# SCH.net
KiCad netlist of a schematic drawn in Altium Designer
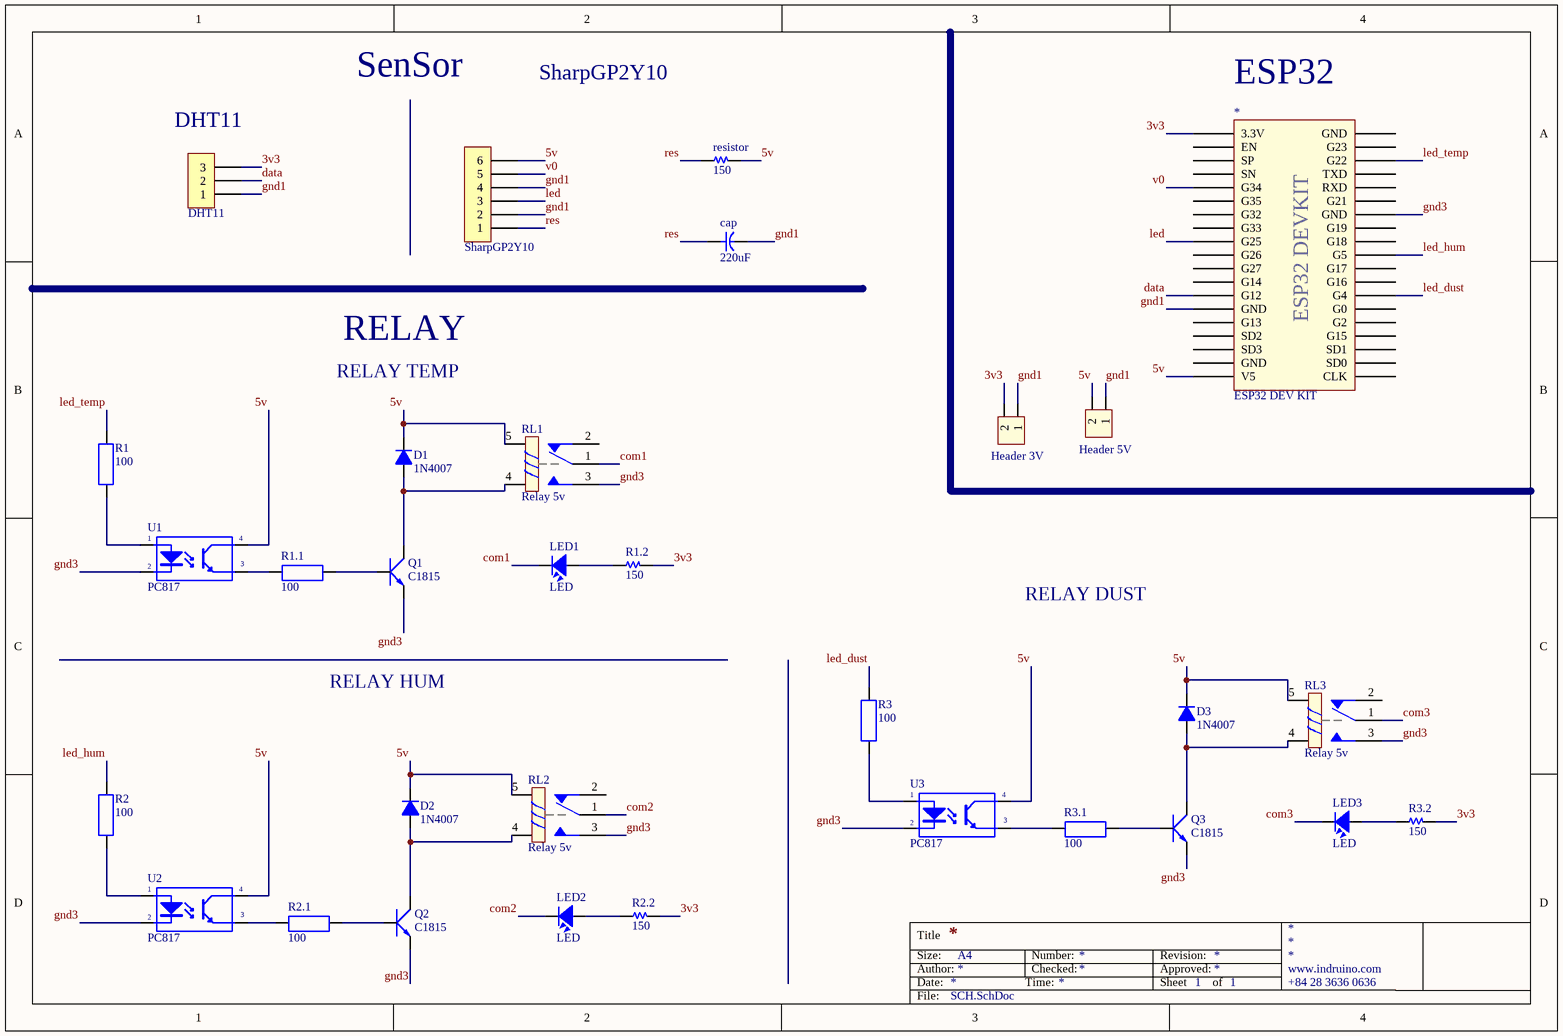
[diagram p0: SCH.SchDoc]

(export (version "E")
  (design (tool "Eeschema 10.0.6"))
  (components
    (comp (ref "*")
      (value "ESP32 DEV KIT")
      (footprint "ESP32 DEVKIT")
      (libsource (lib "Module") (part "ESP32 DEV KIT"))
    )
    (comp (ref "cap")
      (value "220uF")
      (footprint "CYL/D.250/LS.100")
      (description "Capacitor pol")
      (libsource (lib "chipfc_libs") (part "Capacitor"))
    )
    (comp (ref "D1")
      (value "1N4007")
      (footprint "D0.5A")
      (description "Diode 1A")
      (libsource (lib "SCH_Lib_Devzone") (part "D1A"))
    )
    (comp (ref "D2")
      (value "1N4007")
      (footprint "D0.5A")
      (description "Diode 1A")
      (libsource (lib "SCH_Lib_Devzone") (part "D1A"))
    )
    (comp (ref "D3")
      (value "1N4007")
      (footprint "D0.5A")
      (description "Diode 1A")
      (libsource (lib "SCH_Lib_Devzone") (part "D1A"))
    )
    (comp (ref "DHT11")
      (value "DHT11")
      (footprint "XH2.54M-3")
      (description "Cắm")
      (libsource (lib "Header") (part "Header 3P 2.54 Duc Thang"))
    )
    (comp (ref "Header 3V")
      (value "Header 3V")
      (footprint "XH2.54M-2")
      (description "Cắm")
      (libsource (lib "Header") (part "Header 2P 2.54 Duc Thang"))
    )
    (comp (ref "Header 5V")
      (value "Header 5V")
      (footprint "XH2.54M-2")
      (description "Cắm")
      (libsource (lib "Header") (part "Header 2P 2.54 Duc Thang"))
    )
    (comp (ref "LED1")
      (value "LED")
      (footprint "led5mm_yellow")
      (description "LED Single colour Green and Red")
      (libsource (lib "Compiled_Devzone") (part "LED"))
    )
    (comp (ref "LED2")
      (value "LED")
      (footprint "led5mm_yellow")
      (description "LED Single colour Green and Red")
      (libsource (lib "Compiled_Devzone") (part "LED"))
    )
    (comp (ref "LED3")
      (value "LED")
      (footprint "led5mm_yellow")
      (description "LED Single colour Green and Red")
      (libsource (lib "Compiled_Devzone") (part "LED"))
    )
    (comp (ref "Q1")
      (value "C1815")
      (footprint "QTO-92")
      (description "NPN 600mW, ECB")
      (libsource (lib "SCH_Lib_Devzone") (part "C1815"))
    )
    (comp (ref "Q2")
      (value "C1815")
      (footprint "QTO-92")
      (description "NPN 600mW, ECB")
      (libsource (lib "SCH_Lib_Devzone") (part "C1815"))
    )
    (comp (ref "Q3")
      (value "C1815")
      (footprint "QTO-92")
      (description "NPN 600mW, ECB")
      (libsource (lib "SCH_Lib_Devzone") (part "C1815"))
    )
    (comp (ref "R1")
      (value "100")
      (footprint "Res_15mm")
      (description "Resistor 1W")
      (libsource (lib "SCH_Lib_Devzone") (part "R1W"))
    )
    (comp (ref "R1.1")
      (value "100")
      (footprint "Res_15mm")
      (description "Resistor 1W")
      (libsource (lib "SCH_Lib_Devzone") (part "R1W"))
    )
    (comp (ref "R1.2")
      (value "150")
      (footprint "R 1/4W/300")
      (description "Resistor")
      (libsource (lib "chipfc_libs") (part "Resistor"))
    )
    (comp (ref "R2")
      (value "100")
      (footprint "Res_15mm")
      (description "Resistor 1W")
      (libsource (lib "SCH_Lib_Devzone") (part "R1W"))
    )
    (comp (ref "R2.1")
      (value "100")
      (footprint "Res_15mm")
      (description "Resistor 1W")
      (libsource (lib "SCH_Lib_Devzone") (part "R1W"))
    )
    (comp (ref "R2.2")
      (value "150")
      (footprint "R 1/4W/300")
      (description "Resistor")
      (libsource (lib "chipfc_libs") (part "Resistor"))
    )
    (comp (ref "R3")
      (value "100")
      (footprint "Res_15mm")
      (description "Resistor 1W")
      (libsource (lib "SCH_Lib_Devzone") (part "R1W"))
    )
    (comp (ref "R3.1")
      (value "100")
      (footprint "Res_15mm")
      (description "Resistor 1W")
      (libsource (lib "SCH_Lib_Devzone") (part "R1W"))
    )
    (comp (ref "R3.2")
      (value "150")
      (footprint "R 1/4W/300")
      (description "Resistor")
      (libsource (lib "chipfc_libs") (part "Resistor"))
    )
    (comp (ref "resistor")
      (value "150")
      (footprint "R 1/4W/300")
      (description "Resistor")
      (libsource (lib "chipfc_libs") (part "Resistor"))
    )
    (comp (ref "RL1")
      (value "Relay 5v")
      (footprint "RL_SPDT_10A")
      (description "Relay SPDT,10A - 12VDC 5 Pin")
      (libsource (lib "Compiled_Devzone") (part "Relay 1"))
    )
    (comp (ref "RL2")
      (value "Relay 5v")
      (footprint "RL_SPDT_10A")
      (description "Relay SPDT,10A - 12VDC 5 Pin")
      (libsource (lib "Compiled_Devzone") (part "Relay 1"))
    )
    (comp (ref "RL3")
      (value "Relay 5v")
      (footprint "RL_SPDT_10A")
      (description "Relay SPDT,10A - 12VDC 5 Pin")
      (libsource (lib "Compiled_Devzone") (part "Relay 1"))
    )
    (comp (ref "SharpGP2Y10")
      (value "SharpGP2Y10")
      (footprint "XH2.54M-6")
      (description "Cắm")
      (libsource (lib "Header") (part "Header 6P 2.54 Duc Thang"))
    )
    (comp (ref "U1")
      (value "PC817")
      (footprint "DIP4/W0.3")
      (description "Single Opto")
      (libsource (lib "SCH_Lib_Devzone") (part "PC817"))
    )
    (comp (ref "U2")
      (value "PC817")
      (footprint "DIP4/W0.3")
      (description "Single Opto")
      (libsource (lib "SCH_Lib_Devzone") (part "PC817"))
    )
    (comp (ref "U3")
      (value "PC817")
      (footprint "DIP4/W0.3")
      (description "Single Opto")
      (libsource (lib "SCH_Lib_Devzone") (part "PC817"))
    )
  )
  (nets
    (net (code "1") (name "/3v3") (class "Default")
      (node (ref "*") (pin "1") (pinfunction "3.3V_1") (pintype "passive"))
      (node (ref "DHT11") (pin "3") (pinfunction "3_3") (pintype "passive"))
      (node (ref "Header 3V") (pin "2") (pinfunction "2_2") (pintype "passive"))
      (node (ref "R1.2") (pin "2") (pinfunction "2_2") (pintype "passive"))
      (node (ref "R2.2") (pin "2") (pinfunction "2_2") (pintype "passive"))
      (node (ref "R3.2") (pin "2") (pinfunction "2_2") (pintype "passive"))
    )
    (net (code "2") (name "/5v") (class "Default")
      (node (ref "*") (pin "19") (pinfunction "V5_19") (pintype "passive"))
      (node (ref "D1") (pin "2") (pinfunction "K_2") (pintype "passive"))
      (node (ref "D2") (pin "2") (pinfunction "K_2") (pintype "passive"))
      (node (ref "D3") (pin "2") (pinfunction "K_2") (pintype "passive"))
      (node (ref "Header 5V") (pin "2") (pinfunction "2_2") (pintype "passive"))
      (node (ref "RL1") (pin "5") (pinfunction "5_5") (pintype "passive"))
      (node (ref "RL2") (pin "5") (pinfunction "5_5") (pintype "passive"))
      (node (ref "RL3") (pin "5") (pinfunction "5_5") (pintype "passive"))
      (node (ref "SharpGP2Y10") (pin "6") (pinfunction "6_6") (pintype "passive"))
      (node (ref "U1") (pin "4") (pinfunction "C_4") (pintype "passive"))
      (node (ref "U2") (pin "4") (pinfunction "C_4") (pintype "passive"))
      (node (ref "U3") (pin "4") (pinfunction "C_4") (pintype "passive"))
      (node (ref "resistor") (pin "2") (pinfunction "2_2") (pintype "passive"))
    )
    (net (code "4") (name "/com1") (class "Default")
      (node (ref "LED1") (pin "2") (pinfunction "2_2") (pintype "passive"))
      (node (ref "RL1") (pin "1") (pinfunction "1_1") (pintype "passive"))
    )
    (net (code "5") (name "/com2") (class "Default")
      (node (ref "LED2") (pin "2") (pinfunction "2_2") (pintype "passive"))
      (node (ref "RL2") (pin "1") (pinfunction "1_1") (pintype "passive"))
    )
    (net (code "6") (name "/com3") (class "Default")
      (node (ref "LED3") (pin "2") (pinfunction "2_2") (pintype "passive"))
      (node (ref "RL3") (pin "1") (pinfunction "1_1") (pintype "passive"))
    )
    (net (code "7") (name "/data") (class "Default")
      (node (ref "*") (pin "13") (pinfunction "G12_13") (pintype "passive"))
      (node (ref "DHT11") (pin "2") (pinfunction "2_2") (pintype "passive"))
    )
    (net (code "8") (name "/gnd1") (class "Default")
      (node (ref "*") (pin "14") (pinfunction "GND_14") (pintype "passive"))
      (node (ref "DHT11") (pin "1") (pinfunction "1_1") (pintype "passive"))
      (node (ref "Header 3V") (pin "1") (pinfunction "1_1") (pintype "passive"))
      (node (ref "Header 5V") (pin "1") (pinfunction "1_1") (pintype "passive"))
      (node (ref "SharpGP2Y10") (pin "2") (pinfunction "2_2") (pintype "passive"))
      (node (ref "SharpGP2Y10") (pin "4") (pinfunction "4_4") (pintype "passive"))
      (node (ref "cap") (pin "2") (pinfunction "2_2") (pintype "passive"))
    )
    (net (code "9") (name "/gnd3") (class "Default")
      (node (ref "*") (pin "32") (pinfunction "GND_32") (pintype "passive"))
      (node (ref "Q1") (pin "1") (pinfunction "E_1") (pintype "passive"))
      (node (ref "Q2") (pin "1") (pinfunction "E_1") (pintype "passive"))
      (node (ref "Q3") (pin "1") (pinfunction "E_1") (pintype "passive"))
      (node (ref "RL1") (pin "3") (pinfunction "3_3") (pintype "passive"))
      (node (ref "RL2") (pin "3") (pinfunction "3_3") (pintype "passive"))
      (node (ref "RL3") (pin "3") (pinfunction "3_3") (pintype "passive"))
      (node (ref "U1") (pin "2") (pinfunction "K_2") (pintype "passive"))
      (node (ref "U2") (pin "2") (pinfunction "K_2") (pintype "passive"))
      (node (ref "U3") (pin "2") (pinfunction "K_2") (pintype "passive"))
    )
    (net (code "10") (name "/led") (class "Default")
      (node (ref "*") (pin "9") (pinfunction "G25_9") (pintype "passive"))
      (node (ref "SharpGP2Y10") (pin "3") (pinfunction "3_3") (pintype "passive"))
    )
    (net (code "11") (name "/led_dust") (class "Default")
      (node (ref "*") (pin "26") (pinfunction "G4_26") (pintype "passive"))
      (node (ref "R3") (pin "2") (pinfunction "2_2") (pintype "passive"))
    )
    (net (code "12") (name "/led_hum") (class "Default")
      (node (ref "*") (pin "29") (pinfunction "G5_29") (pintype "passive"))
      (node (ref "R2") (pin "2") (pinfunction "2_2") (pintype "passive"))
    )
    (net (code "13") (name "/led_temp") (class "Default")
      (node (ref "*") (pin "36") (pinfunction "G22_36") (pintype "passive"))
      (node (ref "R1") (pin "2") (pinfunction "2_2") (pintype "passive"))
    )
    (net (code "14") (name "/res") (class "Default")
      (node (ref "SharpGP2Y10") (pin "1") (pinfunction "1_1") (pintype "passive"))
      (node (ref "cap") (pin "1") (pinfunction "1_1") (pintype "passive"))
      (node (ref "resistor") (pin "1") (pinfunction "1_1") (pintype "passive"))
    )
    (net (code "15") (name "/v0") (class "Default")
      (node (ref "*") (pin "5") (pinfunction "G34_5") (pintype "passive"))
      (node (ref "SharpGP2Y10") (pin "5") (pinfunction "5_5") (pintype "passive"))
    )
    (net (code "16") (name "Net-(D1-A)") (class "Default")
      (node (ref "D1") (pin "1") (pinfunction "A_1") (pintype "passive"))
      (node (ref "Q1") (pin "2") (pinfunction "C_2") (pintype "passive"))
      (node (ref "RL1") (pin "4") (pinfunction "4_4") (pintype "passive"))
    )
    (net (code "17") (name "Net-(D2-A)") (class "Default")
      (node (ref "D2") (pin "1") (pinfunction "A_1") (pintype "passive"))
      (node (ref "Q2") (pin "2") (pinfunction "C_2") (pintype "passive"))
      (node (ref "RL2") (pin "4") (pinfunction "4_4") (pintype "passive"))
    )
    (net (code "18") (name "Net-(D3-A)") (class "Default")
      (node (ref "D3") (pin "1") (pinfunction "A_1") (pintype "passive"))
      (node (ref "Q3") (pin "2") (pinfunction "C_2") (pintype "passive"))
      (node (ref "RL3") (pin "4") (pinfunction "4_4") (pintype "passive"))
    )
    (net (code "19") (name "Net-(LED1-Pad1)") (class "Default")
      (node (ref "LED1") (pin "1") (pinfunction "1_1") (pintype "passive"))
      (node (ref "R1.2") (pin "1") (pinfunction "1_1") (pintype "passive"))
    )
    (net (code "20") (name "Net-(LED2-Pad1)") (class "Default")
      (node (ref "LED2") (pin "1") (pinfunction "1_1") (pintype "passive"))
      (node (ref "R2.2") (pin "1") (pinfunction "1_1") (pintype "passive"))
    )
    (net (code "21") (name "Net-(LED3-Pad1)") (class "Default")
      (node (ref "LED3") (pin "1") (pinfunction "1_1") (pintype "passive"))
      (node (ref "R3.2") (pin "1") (pinfunction "1_1") (pintype "passive"))
    )
    (net (code "22") (name "Net-(Q1-B)") (class "Default")
      (node (ref "Q1") (pin "3") (pinfunction "B_3") (pintype "passive"))
      (node (ref "R1.1") (pin "1") (pinfunction "1_1") (pintype "passive"))
    )
    (net (code "23") (name "Net-(Q2-B)") (class "Default")
      (node (ref "Q2") (pin "3") (pinfunction "B_3") (pintype "passive"))
      (node (ref "R2.1") (pin "1") (pinfunction "1_1") (pintype "passive"))
    )
    (net (code "24") (name "Net-(Q3-B)") (class "Default")
      (node (ref "Q3") (pin "3") (pinfunction "B_3") (pintype "passive"))
      (node (ref "R3.1") (pin "1") (pinfunction "1_1") (pintype "passive"))
    )
    (net (code "25") (name "Net-(U1-A)") (class "Default")
      (node (ref "R1") (pin "1") (pinfunction "1_1") (pintype "passive"))
      (node (ref "U1") (pin "1") (pinfunction "A_1") (pintype "passive"))
    )
    (net (code "26") (name "Net-(U1-E)") (class "Default")
      (node (ref "R1.1") (pin "2") (pinfunction "2_2") (pintype "passive"))
      (node (ref "U1") (pin "3") (pinfunction "E_3") (pintype "passive"))
    )
    (net (code "27") (name "Net-(U2-A)") (class "Default")
      (node (ref "R2") (pin "1") (pinfunction "1_1") (pintype "passive"))
      (node (ref "U2") (pin "1") (pinfunction "A_1") (pintype "passive"))
    )
    (net (code "28") (name "Net-(U2-E)") (class "Default")
      (node (ref "R2.1") (pin "2") (pinfunction "2_2") (pintype "passive"))
      (node (ref "U2") (pin "3") (pinfunction "E_3") (pintype "passive"))
    )
    (net (code "29") (name "Net-(U3-A)") (class "Default")
      (node (ref "R3") (pin "1") (pinfunction "1_1") (pintype "passive"))
      (node (ref "U3") (pin "1") (pinfunction "A_1") (pintype "passive"))
    )
    (net (code "30") (name "Net-(U3-E)") (class "Default")
      (node (ref "R3.1") (pin "2") (pinfunction "2_2") (pintype "passive"))
      (node (ref "U3") (pin "3") (pinfunction "E_3") (pintype "passive"))
    )
    (net (code "31") (name "unconnected-(*-CLK-Pad20)") (class "Default")
      (node (ref "*") (pin "20") (pinfunction "CLK_20") (pintype "passive"))
    )
    (net (code "32") (name "unconnected-(*-EN-Pad2)") (class "Default")
      (node (ref "*") (pin "2") (pinfunction "EN_2") (pintype "passive"))
    )
    (net (code "33") (name "unconnected-(*-G0-Pad25)") (class "Default")
      (node (ref "*") (pin "25") (pinfunction "G0_25") (pintype "passive"))
    )
    (net (code "34") (name "unconnected-(*-G2-Pad24)") (class "Default")
      (node (ref "*") (pin "24") (pinfunction "G2_24") (pintype "passive"))
    )
    (net (code "35") (name "unconnected-(*-G13-Pad15)") (class "Default")
      (node (ref "*") (pin "15") (pinfunction "G13_15") (pintype "passive"))
    )
    (net (code "36") (name "unconnected-(*-G14-Pad12)") (class "Default")
      (node (ref "*") (pin "12") (pinfunction "G14_12") (pintype "passive"))
    )
    (net (code "37") (name "unconnected-(*-G15-Pad23)") (class "Default")
      (node (ref "*") (pin "23") (pinfunction "G15_23") (pintype "passive"))
    )
    (net (code "38") (name "unconnected-(*-G16-Pad27)") (class "Default")
      (node (ref "*") (pin "27") (pinfunction "G16_27") (pintype "passive"))
    )
    (net (code "39") (name "unconnected-(*-G17-Pad28)") (class "Default")
      (node (ref "*") (pin "28") (pinfunction "G17_28") (pintype "passive"))
    )
    (net (code "40") (name "unconnected-(*-G18-Pad30)") (class "Default")
      (node (ref "*") (pin "30") (pinfunction "G18_30") (pintype "passive"))
    )
    (net (code "41") (name "unconnected-(*-G19-Pad31)") (class "Default")
      (node (ref "*") (pin "31") (pinfunction "G19_31") (pintype "passive"))
    )
    (net (code "42") (name "unconnected-(*-G21-Pad33)") (class "Default")
      (node (ref "*") (pin "33") (pinfunction "G21_33") (pintype "passive"))
    )
    (net (code "43") (name "unconnected-(*-G23-Pad37)") (class "Default")
      (node (ref "*") (pin "37") (pinfunction "G23_37") (pintype "passive"))
    )
    (net (code "44") (name "unconnected-(*-G26-Pad10)") (class "Default")
      (node (ref "*") (pin "10") (pinfunction "G26_10") (pintype "passive"))
    )
    (net (code "45") (name "unconnected-(*-G27-Pad11)") (class "Default")
      (node (ref "*") (pin "11") (pinfunction "G27_11") (pintype "passive"))
    )
    (net (code "46") (name "unconnected-(*-G32-Pad7)") (class "Default")
      (node (ref "*") (pin "7") (pinfunction "G32_7") (pintype "passive"))
    )
    (net (code "47") (name "unconnected-(*-G33-Pad8)") (class "Default")
      (node (ref "*") (pin "8") (pinfunction "G33_8") (pintype "passive"))
    )
    (net (code "48") (name "unconnected-(*-G35-Pad6)") (class "Default")
      (node (ref "*") (pin "6") (pinfunction "G35_6") (pintype "passive"))
    )
    (net (code "49") (name "unconnected-(*-GND-Pad18)") (class "Default")
      (node (ref "*") (pin "18") (pinfunction "GND_18") (pintype "passive"))
    )
    (net (code "50") (name "unconnected-(*-GND-Pad38)") (class "Default")
      (node (ref "*") (pin "38") (pinfunction "GND_38") (pintype "passive"))
    )
    (net (code "51") (name "unconnected-(*-RXD-Pad34)") (class "Default")
      (node (ref "*") (pin "34") (pinfunction "RXD_34") (pintype "passive"))
    )
    (net (code "52") (name "unconnected-(*-SD0-Pad21)") (class "Default")
      (node (ref "*") (pin "21") (pinfunction "SD0_21") (pintype "passive"))
    )
    (net (code "53") (name "unconnected-(*-SD1-Pad22)") (class "Default")
      (node (ref "*") (pin "22") (pinfunction "SD1_22") (pintype "passive"))
    )
    (net (code "54") (name "unconnected-(*-SD2-Pad16)") (class "Default")
      (node (ref "*") (pin "16") (pinfunction "SD2_16") (pintype "passive"))
    )
    (net (code "55") (name "unconnected-(*-SD3-Pad17)") (class "Default")
      (node (ref "*") (pin "17") (pinfunction "SD3_17") (pintype "passive"))
    )
    (net (code "56") (name "unconnected-(*-SN-Pad4)") (class "Default")
      (node (ref "*") (pin "4") (pinfunction "SN_4") (pintype "passive"))
    )
    (net (code "57") (name "unconnected-(*-SP-Pad3)") (class "Default")
      (node (ref "*") (pin "3") (pinfunction "SP_3") (pintype "passive"))
    )
    (net (code "58") (name "unconnected-(*-TXD-Pad35)") (class "Default")
      (node (ref "*") (pin "35") (pinfunction "TXD_35") (pintype "passive"))
    )
    (net (code "59") (name "unconnected-(RL1-Pad2)") (class "Default")
      (node (ref "RL1") (pin "2") (pinfunction "2_2") (pintype "passive"))
    )
    (net (code "60") (name "unconnected-(RL2-Pad2)") (class "Default")
      (node (ref "RL2") (pin "2") (pinfunction "2_2") (pintype "passive"))
    )
    (net (code "61") (name "unconnected-(RL3-Pad2)") (class "Default")
      (node (ref "RL3") (pin "2") (pinfunction "2_2") (pintype "passive"))
    )
  )
)
